# Output_protection.net
KiCad netlist of a schematic drawn in Altium Designer
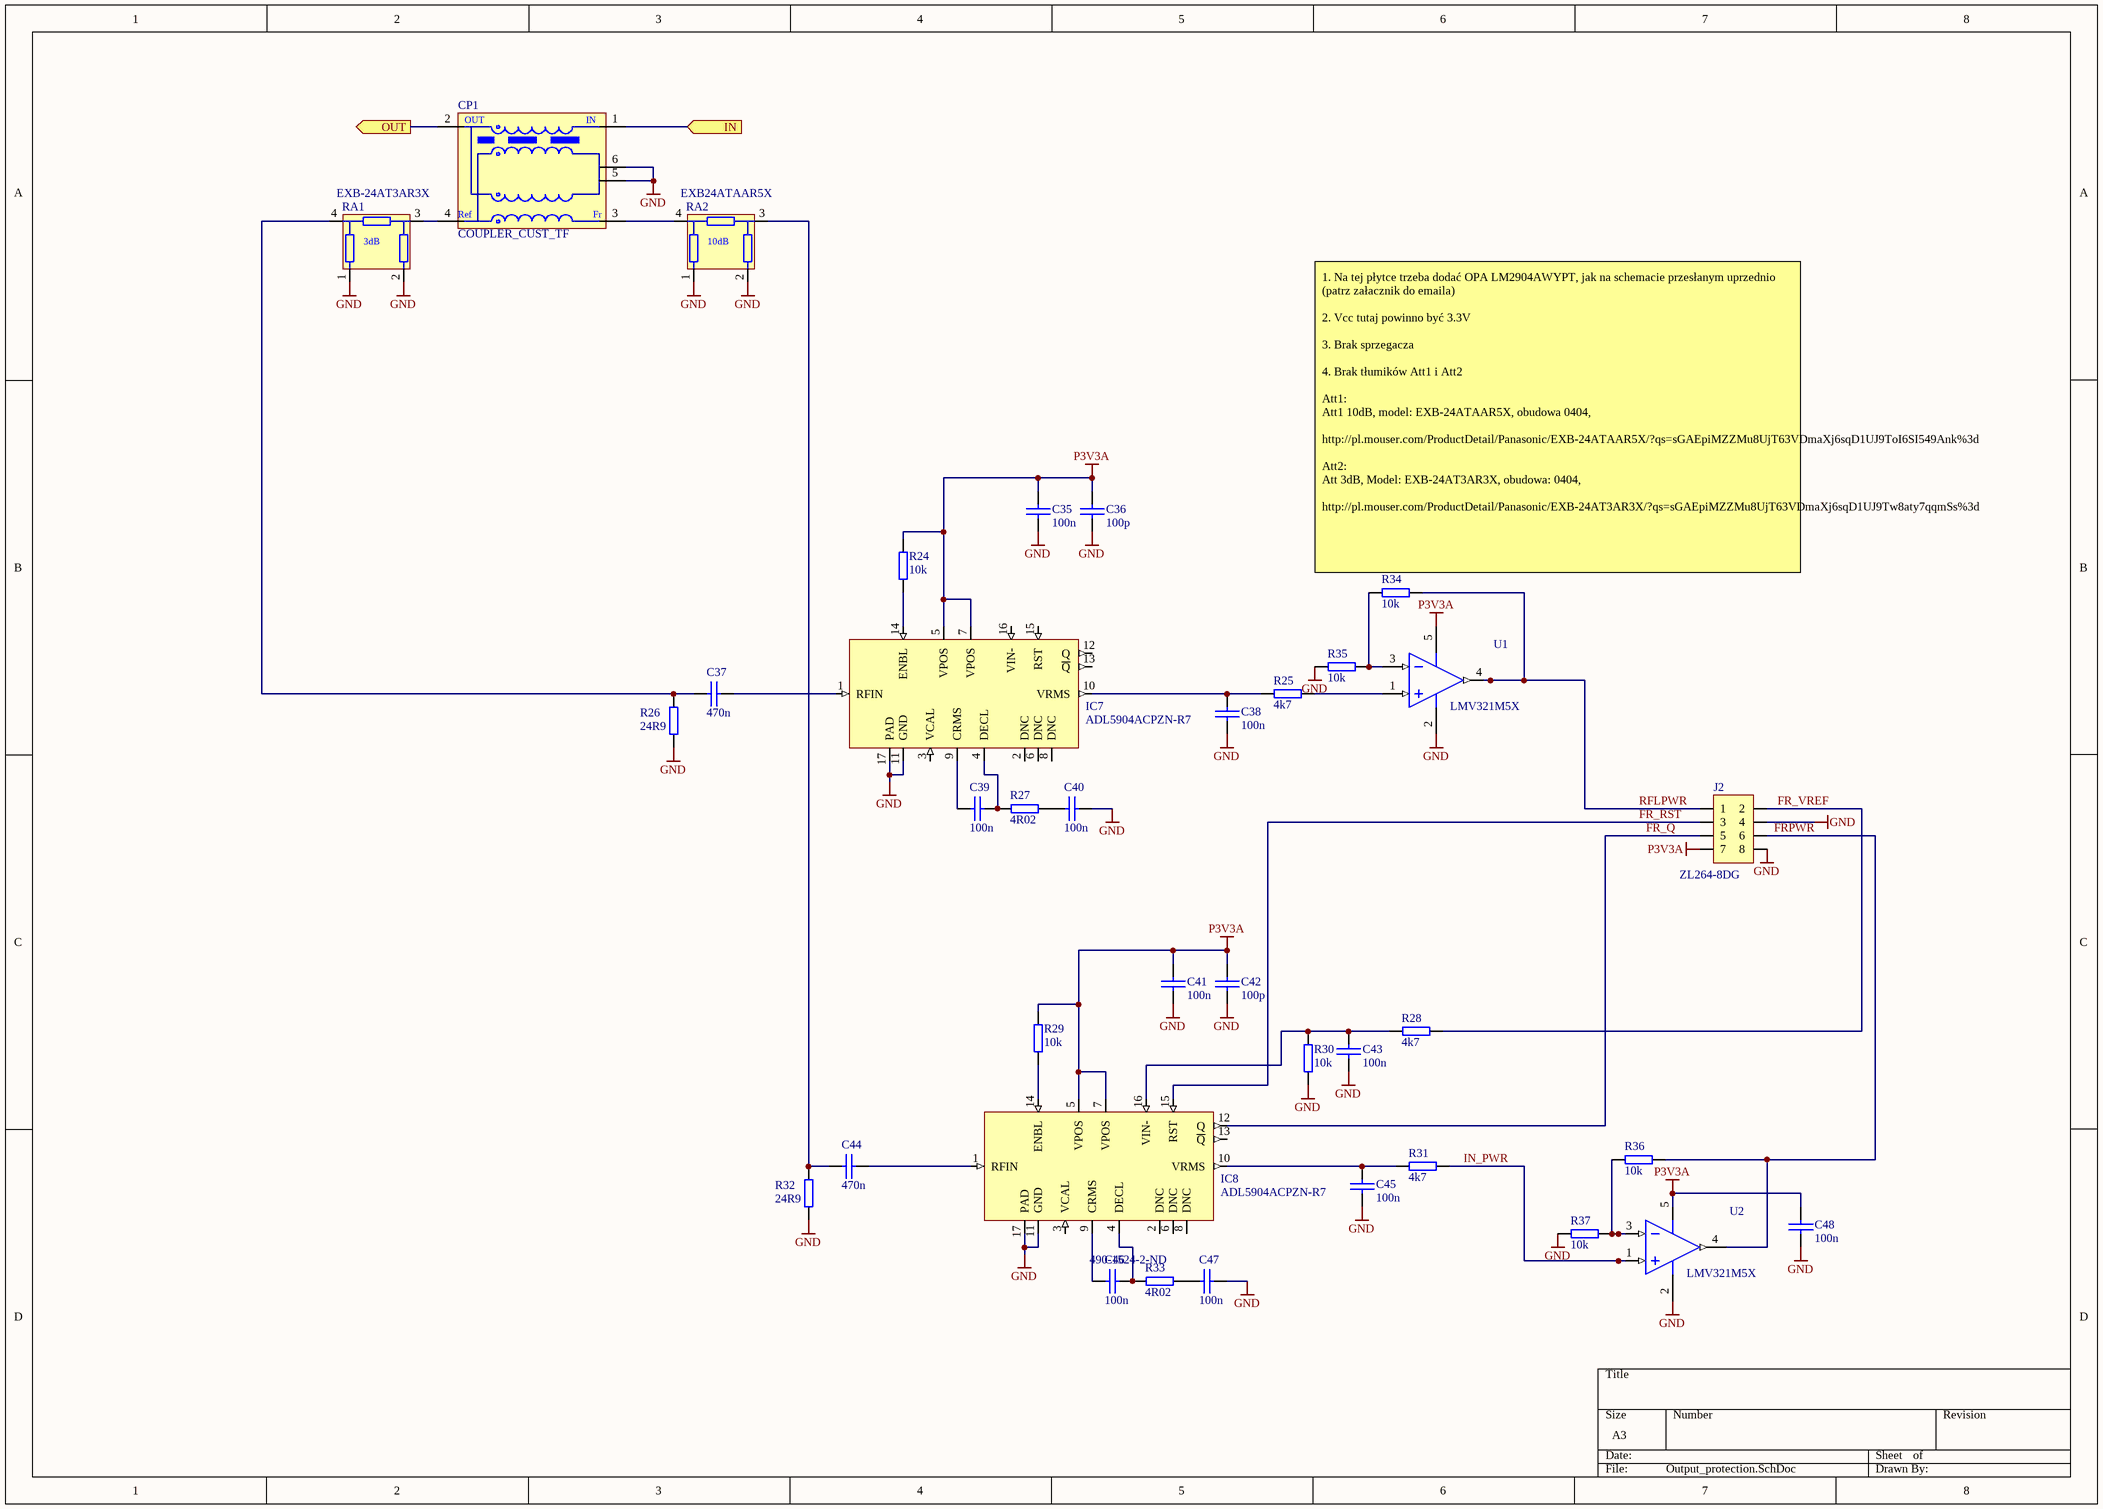
[diagram p0: Output_protection.SchDoc]

(export (version "E")
  (design (tool "Eeschema 10.0.6"))
  (components
    (comp (ref "C35")
      (value "100n")
      (footprint "0603C")
      (description "Capacitor SMD")
      (fields (field (name "PART") "GRM188L81H104KA93D"))
      (libsource (lib "LIBRARY_SCH") (part "CAP_SMD_0603"))
    )
    (comp (ref "C36")
      (value "100p")
      (footprint "0603C")
      (description "Capacitor SMD")
      (fields (field (name "PART") "C1608NP01H101J080AA"))
      (libsource (lib "LIBRARY_SCH") (part "CAP_SMD_0603"))
    )
    (comp (ref "C37")
      (value "470n")
      (footprint "0603C")
      (description "Capacitor SMD")
      (fields (field (name "PART") "GRM188R71A474KA61D"))
      (libsource (lib "LIBRARY_SCH") (part "CAP_SMD_0603"))
    )
    (comp (ref "C38")
      (value "100n")
      (footprint "0603C")
      (description "Capacitor SMD")
      (fields (field (name "PART") "GRM188L81H104KA93D"))
      (libsource (lib "LIBRARY_SCH") (part "CAP_SMD_0603"))
    )
    (comp (ref "C39")
      (value "100n")
      (footprint "0603C")
      (description "Capacitor SMD")
      (fields (field (name "PART") "GRM188L81H104KA93D"))
      (libsource (lib "LIBRARY_SCH") (part "CAP_SMD_0603"))
    )
    (comp (ref "C40")
      (value "100n")
      (footprint "0603C")
      (description "Capacitor SMD")
      (fields (field (name "PART") "GRM188L81H104KA93D"))
      (libsource (lib "LIBRARY_SCH") (part "CAP_SMD_0603"))
    )
    (comp (ref "C41")
      (value "100n")
      (footprint "0603C")
      (description "Capacitor SMD")
      (fields (field (name "PART") "GRM188L81H104KA93D"))
      (libsource (lib "LIBRARY_SCH") (part "CAP_SMD_0603"))
    )
    (comp (ref "C42")
      (value "100p")
      (footprint "0603C")
      (description "Capacitor SMD")
      (fields (field (name "PART") "C1608NP01H101J080AA"))
      (libsource (lib "LIBRARY_SCH") (part "CAP_SMD_0603"))
    )
    (comp (ref "C43")
      (value "100n")
      (footprint "0603C")
      (description "Capacitor SMD")
      (fields (field (name "PART") "GRM188L81H104KA93D"))
      (libsource (lib "LIBRARY_SCH") (part "CAP_SMD_0603"))
    )
    (comp (ref "C44")
      (value "470n")
      (footprint "0603C")
      (description "Capacitor SMD")
      (fields (field (name "PART") "GRM188R71A474KA61D"))
      (libsource (lib "LIBRARY_SCH") (part "CAP_SMD_0603"))
    )
    (comp (ref "C45")
      (value "100n")
      (footprint "0603C")
      (description "Capacitor SMD")
      (fields (field (name "PART") "GRM188L81H104KA93D"))
      (libsource (lib "LIBRARY_SCH") (part "CAP_SMD_0603"))
    )
    (comp (ref "C46")
      (value "100n")
      (footprint "0603C")
      (description "Capacitor SMD")
      (fields
        (field (name "SUPPLIER PART NUMBER 1") "490-1524-2-ND")
        (field (name "PART") "GRM188L81H104KA93D")
      )
      (libsource (lib "LIBRARY_SCH") (part "CAP_SMD_0603"))
    )
    (comp (ref "C47")
      (value "100n")
      (footprint "0603C")
      (description "Capacitor SMD")
      (fields (field (name "PART") "GRM188L81H104KA93D"))
      (libsource (lib "LIBRARY_SCH") (part "CAP_SMD_0603"))
    )
    (comp (ref "C48")
      (value "100n")
      (footprint "0603C")
      (description "Capacitor SMD")
      (fields (field (name "PART") "GRM188L81H104KA93D"))
      (libsource (lib "LIBRARY_SCH") (part "CAP_SMD_0603"))
    )
    (comp (ref "CP1")
      (value "COUPLER_CUST_TF")
      (footprint "COUPLER_CUST_TF")
      (description "custom coupler")
      (libsource (lib "LIBRARY_SCH") (part "IND_COUPLER_TF"))
    )
    (comp (ref "IC7")
      (value "ADL5904ACPZN-R7")
      (footprint "QFN50P300X300X80_HS-17N")
      (description "DC   to 6 GHz  , 45 dB DC  to 6 GHz , 45 dB TruPwr Detector with Envelope Threshold Detection")
      (libsource (lib "LIBRARY_SCH") (part "ADL5904"))
    )
    (comp (ref "IC8")
      (value "ADL5904ACPZN-R7")
      (footprint "QFN50P300X300X80_HS-17N")
      (description "DC   to 6 GHz  , 45 dB DC  to 6 GHz , 45 dB TruPwr Detector with Envelope Threshold Detection")
      (libsource (lib "LIBRARY_SCH") (part "ADL5904"))
    )
    (comp (ref "J2")
      (value "ZL264-8DG")
      (footprint "ZL264-8DG")
      (description "2.54mm pitch connector")
      (libsource (lib "LIBRARY_SCH") (part "CON_2X4 2.54 SMT FEM"))
    )
    (comp (ref "R24")
      (value "10k")
      (footprint "0603R")
      (description "SMD Resistor")
      (fields (field (name "PART") "CRCW060310K0FKEA"))
      (libsource (lib "LIBRARY_SCH") (part "RES_0603"))
    )
    (comp (ref "R25")
      (value "4k7")
      (footprint "0603R")
      (description "SMD Resistor")
      (fields (field (name "PART") "CR0603-FX-4701ELF"))
      (libsource (lib "LIBRARY_SCH") (part "RES_0603"))
    )
    (comp (ref "R26")
      (value "24R9")
      (footprint "0603R")
      (description "SMD Resistor")
      (fields (field (name "PART") "CPF0603F24R9C1"))
      (libsource (lib "LIBRARY_SCH") (part "RES_0603"))
    )
    (comp (ref "R27")
      (value "4R02")
      (footprint "0603R")
      (description "SMD Resistor")
      (fields (field (name "PART") "CRCW06034R02FKEA"))
      (libsource (lib "LIBRARY_SCH") (part "RES_0603"))
    )
    (comp (ref "R28")
      (value "4k7")
      (footprint "0603R")
      (description "SMD Resistor")
      (fields (field (name "PART") "CR0603-FX-4701ELF"))
      (libsource (lib "LIBRARY_SCH") (part "RES_0603"))
    )
    (comp (ref "R29")
      (value "10k")
      (footprint "0603R")
      (description "SMD Resistor")
      (fields (field (name "PART") "CRCW060310K0FKEA"))
      (libsource (lib "LIBRARY_SCH") (part "RES_0603"))
    )
    (comp (ref "R30")
      (value "10k")
      (footprint "0603R")
      (description "SMD Resistor")
      (fields (field (name "PART") "CRCW060310K0FKEA"))
      (libsource (lib "LIBRARY_SCH") (part "RES_0603"))
    )
    (comp (ref "R31")
      (value "4k7")
      (footprint "0603R")
      (description "SMD Resistor")
      (fields (field (name "PART") "CR0603-FX-4701ELF"))
      (libsource (lib "LIBRARY_SCH") (part "RES_0603"))
    )
    (comp (ref "R32")
      (value "24R9")
      (footprint "0603R")
      (description "SMD Resistor")
      (fields (field (name "PART") "CPF0603F24R9C1"))
      (libsource (lib "LIBRARY_SCH") (part "RES_0603"))
    )
    (comp (ref "R33")
      (value "4R02")
      (footprint "0603R")
      (description "SMD Resistor")
      (libsource (lib "LIBRARY_SCH") (part "RES_0603"))
    )
    (comp (ref "R34")
      (value "10k")
      (footprint "0603R")
      (description "SMD Resistor")
      (fields (field (name "PART") "CRCW060310K0FKEA"))
      (libsource (lib "LIBRARY_SCH") (part "RES_0603"))
    )
    (comp (ref "R35")
      (value "10k")
      (footprint "0603R")
      (description "SMD Resistor")
      (fields (field (name "PART") "CRCW060310K0FKEA"))
      (libsource (lib "LIBRARY_SCH") (part "RES_0603"))
    )
    (comp (ref "R36")
      (value "10k")
      (footprint "0603R")
      (description "SMD Resistor")
      (fields (field (name "PART") "CRCW060310K0FKEA"))
      (libsource (lib "LIBRARY_SCH") (part "RES_0603"))
    )
    (comp (ref "R37")
      (value "10k")
      (footprint "0603R")
      (description "SMD Resistor")
      (fields (field (name "PART") "CRCW060310K0FKEA"))
      (libsource (lib "LIBRARY_SCH") (part "RES_0603"))
    )
    (comp (ref "RA1")
      (value "EXB-24AT3AR3X")
      (footprint "CAC-65P100X100-4L")
      (description "3dB Chip Attenuator")
      (libsource (lib "LIBRARY_SCH") (part "RES_ATT_3dB"))
    )
    (comp (ref "RA2")
      (value "EXB24ATAAR5X")
      (footprint "CAC-65P100X100-4L")
      (description "10dB Chip Attenuator")
      (libsource (lib "LIBRARY_SCH") (part "RES_ATT_10dB"))
    )
    (comp (ref "U1")
      (value "LMV321M5X")
      (footprint "DBV0005A_N")
      (description "General Purpose, Low Voltage, Rail-to-Rail Output Operational Amplifiers, 5-pin SOT-23")
      (fields (field (name "MANUFACTURER") "Texas Instruments"))
      (libsource (lib "Altium Content Vault") (part "AMP-OPA-LMV551-5"))
    )
    (comp (ref "U2")
      (value "LMV321M5X")
      (footprint "DBV0005A_N")
      (description "General Purpose, Low Voltage, Rail-to-Rail Output Operational Amplifiers, 5-pin SOT-23")
      (fields (field (name "MANUFACTURER") "Texas Instruments"))
      (libsource (lib "Altium Content Vault") (part "AMP-OPA-LMV551-5"))
    )
  )
  (nets
    (net (code "1") (name "/FRPWR") (class "Default")
      (node (ref "J2") (pin "6") (pinfunction "6_6") (pintype "passive"))
      (node (ref "R36") (pin "1") (pinfunction "1_1") (pintype "passive"))
      (node (ref "U2") (pin "4") (pinfunction "OUT_4") (pintype "output"))
    )
    (net (code "2") (name "/FR_Q") (class "Default")
      (node (ref "IC8") (pin "12") (pinfunction "Q_12") (pintype "output"))
      (node (ref "J2") (pin "5") (pinfunction "5_5") (pintype "passive"))
    )
    (net (code "3") (name "/FR_RST") (class "Default")
      (node (ref "IC8") (pin "15") (pinfunction "RST_15") (pintype "input"))
      (node (ref "J2") (pin "3") (pinfunction "3_3") (pintype "passive"))
    )
    (net (code "4") (name "/FR_VREF") (class "Default")
      (node (ref "J2") (pin "2") (pinfunction "2_2") (pintype "passive"))
      (node (ref "R28") (pin "1") (pinfunction "1_1") (pintype "passive"))
    )
    (net (code "5") (name "/IN") (class "Default") (node (ref "CP1") (pin "1") (pintype "passive")))
    (net (code "6") (name "/IN_PWR") (class "Default")
      (node (ref "R31") (pin "1") (pinfunction "1_1") (pintype "passive"))
      (node (ref "U2") (pin "1") (pinfunction "IN+_1") (pintype "input"))
    )
    (net (code "7") (name "/OUT") (class "Default") (node (ref "CP1") (pin "2") (pintype "passive")))
    (net (code "8") (name "/RFLPWR") (class "Default")
      (node (ref "J2") (pin "1") (pinfunction "1_1") (pintype "passive"))
      (node (ref "R34") (pin "1") (pinfunction "1_1") (pintype "passive"))
      (node (ref "U1") (pin "4") (pinfunction "OUT_4") (pintype "output"))
    )
    (net (code "9") (name "GND") (class "Default")
      (node (ref "C35") (pin "2") (pinfunction "2_2") (pintype "passive"))
      (node (ref "C36") (pin "2") (pinfunction "2_2") (pintype "passive"))
      (node (ref "C38") (pin "1") (pinfunction "1_1") (pintype "passive"))
      (node (ref "C40") (pin "2") (pinfunction "2_2") (pintype "passive"))
      (node (ref "C41") (pin "2") (pinfunction "2_2") (pintype "passive"))
      (node (ref "C42") (pin "2") (pinfunction "2_2") (pintype "passive"))
      (node (ref "C43") (pin "1") (pinfunction "1_1") (pintype "passive"))
      (node (ref "C45") (pin "1") (pinfunction "1_1") (pintype "passive"))
      (node (ref "C47") (pin "2") (pinfunction "2_2") (pintype "passive"))
      (node (ref "C48") (pin "1") (pinfunction "1_1") (pintype "passive"))
      (node (ref "CP1") (pin "5") (pintype "passive"))
      (node (ref "CP1") (pin "6") (pintype "passive"))
      (node (ref "IC7") (pin "11") (pinfunction "GND_11") (pintype "power_in"))
      (node (ref "IC7") (pin "17") (pinfunction "PAD_17") (pintype "power_in"))
      (node (ref "IC8") (pin "11") (pinfunction "GND_11") (pintype "power_in"))
      (node (ref "IC8") (pin "17") (pinfunction "PAD_17") (pintype "power_in"))
      (node (ref "J2") (pin "4") (pinfunction "4_4") (pintype "passive"))
      (node (ref "J2") (pin "8") (pinfunction "8_8") (pintype "passive"))
      (node (ref "R26") (pin "2") (pinfunction "2_2") (pintype "passive"))
      (node (ref "R30") (pin "1") (pinfunction "1_1") (pintype "passive"))
      (node (ref "R32") (pin "2") (pinfunction "2_2") (pintype "passive"))
      (node (ref "R35") (pin "2") (pinfunction "2_2") (pintype "passive"))
      (node (ref "R37") (pin "2") (pinfunction "2_2") (pintype "passive"))
      (node (ref "RA1") (pin "1") (pinfunction "1_1") (pintype "passive"))
      (node (ref "RA1") (pin "2") (pinfunction "2_2") (pintype "passive"))
      (node (ref "RA2") (pin "1") (pinfunction "1_1") (pintype "passive"))
      (node (ref "RA2") (pin "2") (pinfunction "2_2") (pintype "passive"))
      (node (ref "U1") (pin "2") (pinfunction "V-_2") (pintype "power_in"))
      (node (ref "U2") (pin "2") (pinfunction "V-_2") (pintype "power_in"))
    )
    (net (code "10") (name "Net-(C37-Pad1)") (class "Default")
      (node (ref "C37") (pin "1") (pinfunction "1_1") (pintype "passive"))
      (node (ref "R26") (pin "1") (pinfunction "1_1") (pintype "passive"))
      (node (ref "RA1") (pin "4") (pinfunction "4_4") (pintype "passive"))
    )
    (net (code "11") (name "Net-(C40-Pad1)") (class "Default")
      (node (ref "C40") (pin "1") (pinfunction "1_1") (pintype "passive"))
      (node (ref "R27") (pin "2") (pinfunction "2_2") (pintype "passive"))
    )
    (net (code "12") (name "Net-(C44-Pad1)") (class "Default")
      (node (ref "C44") (pin "1") (pinfunction "1_1") (pintype "passive"))
      (node (ref "R32") (pin "1") (pinfunction "1_1") (pintype "passive"))
      (node (ref "RA2") (pin "3") (pinfunction "3_3") (pintype "passive"))
    )
    (net (code "13") (name "Net-(C47-Pad1)") (class "Default")
      (node (ref "C47") (pin "1") (pinfunction "1_1") (pintype "passive"))
      (node (ref "R33") (pin "2") (pinfunction "2_2") (pintype "passive"))
    )
    (net (code "14") (name "Net-(CP1-Pad3)") (class "Default")
      (node (ref "CP1") (pin "3") (pintype "passive"))
      (node (ref "RA2") (pin "4") (pinfunction "4_4") (pintype "passive"))
    )
    (net (code "15") (name "Net-(CP1-Pad4)") (class "Default")
      (node (ref "CP1") (pin "4") (pintype "passive"))
      (node (ref "RA1") (pin "3") (pinfunction "3_3") (pintype "passive"))
    )
    (net (code "16") (name "Net-(IC7-CRMS)") (class "Default")
      (node (ref "C39") (pin "1") (pinfunction "1_1") (pintype "passive"))
      (node (ref "IC7") (pin "9") (pinfunction "CRMS_9") (pintype "passive"))
    )
    (net (code "17") (name "Net-(IC7-DECL)") (class "Default")
      (node (ref "C39") (pin "2") (pinfunction "2_2") (pintype "passive"))
      (node (ref "IC7") (pin "4") (pinfunction "DECL_4") (pintype "passive"))
      (node (ref "R27") (pin "1") (pinfunction "1_1") (pintype "passive"))
    )
    (net (code "18") (name "Net-(IC7-ENBL)") (class "Default")
      (node (ref "IC7") (pin "14") (pinfunction "ENBL_14") (pintype "input"))
      (node (ref "R24") (pin "2") (pinfunction "2_2") (pintype "passive"))
    )
    (net (code "19") (name "Net-(IC7-RFIN)") (class "Default")
      (node (ref "C37") (pin "2") (pinfunction "2_2") (pintype "passive"))
      (node (ref "IC7") (pin "1") (pinfunction "RFIN_1") (pintype "input"))
    )
    (net (code "20") (name "Net-(IC7-VRMS)") (class "Default")
      (node (ref "C38") (pin "2") (pinfunction "2_2") (pintype "passive"))
      (node (ref "IC7") (pin "10") (pinfunction "VRMS_10") (pintype "output"))
      (node (ref "R25") (pin "2") (pinfunction "2_2") (pintype "passive"))
    )
    (net (code "21") (name "Net-(IC8-CRMS)") (class "Default")
      (node (ref "C46") (pin "1") (pinfunction "1_1") (pintype "passive"))
      (node (ref "IC8") (pin "9") (pinfunction "CRMS_9") (pintype "passive"))
    )
    (net (code "22") (name "Net-(IC8-DECL)") (class "Default")
      (node (ref "C46") (pin "2") (pinfunction "2_2") (pintype "passive"))
      (node (ref "IC8") (pin "4") (pinfunction "DECL_4") (pintype "passive"))
      (node (ref "R33") (pin "1") (pinfunction "1_1") (pintype "passive"))
    )
    (net (code "23") (name "Net-(IC8-ENBL)") (class "Default")
      (node (ref "IC8") (pin "14") (pinfunction "ENBL_14") (pintype "input"))
      (node (ref "R29") (pin "2") (pinfunction "2_2") (pintype "passive"))
    )
    (net (code "24") (name "Net-(IC8-RFIN)") (class "Default")
      (node (ref "C44") (pin "2") (pinfunction "2_2") (pintype "passive"))
      (node (ref "IC8") (pin "1") (pinfunction "RFIN_1") (pintype "input"))
    )
    (net (code "25") (name "Net-(IC8-VIN-)") (class "Default")
      (node (ref "C43") (pin "2") (pinfunction "2_2") (pintype "passive"))
      (node (ref "IC8") (pin "16") (pinfunction "VIN-_16") (pintype "input"))
      (node (ref "R28") (pin "2") (pinfunction "2_2") (pintype "passive"))
      (node (ref "R30") (pin "2") (pinfunction "2_2") (pintype "passive"))
    )
    (net (code "26") (name "Net-(IC8-VRMS)") (class "Default")
      (node (ref "C45") (pin "2") (pinfunction "2_2") (pintype "passive"))
      (node (ref "IC8") (pin "10") (pinfunction "VRMS_10") (pintype "output"))
      (node (ref "R31") (pin "2") (pinfunction "2_2") (pintype "passive"))
    )
    (net (code "27") (name "Net-(U1-IN+)") (class "Default")
      (node (ref "R25") (pin "1") (pinfunction "1_1") (pintype "passive"))
      (node (ref "U1") (pin "1") (pinfunction "IN+_1") (pintype "input"))
    )
    (net (code "28") (name "Net-(U1-IN-)") (class "Default")
      (node (ref "R34") (pin "2") (pinfunction "2_2") (pintype "passive"))
      (node (ref "R35") (pin "1") (pinfunction "1_1") (pintype "passive"))
      (node (ref "U1") (pin "3") (pinfunction "IN-_3") (pintype "input"))
    )
    (net (code "29") (name "Net-(U2-IN-)") (class "Default")
      (node (ref "R36") (pin "2") (pinfunction "2_2") (pintype "passive"))
      (node (ref "R37") (pin "1") (pinfunction "1_1") (pintype "passive"))
      (node (ref "U2") (pin "3") (pinfunction "IN-_3") (pintype "input"))
    )
    (net (code "30") (name "P3V3A") (class "Default")
      (node (ref "C35") (pin "1") (pinfunction "1_1") (pintype "passive"))
      (node (ref "C36") (pin "1") (pinfunction "1_1") (pintype "passive"))
      (node (ref "C41") (pin "1") (pinfunction "1_1") (pintype "passive"))
      (node (ref "C42") (pin "1") (pinfunction "1_1") (pintype "passive"))
      (node (ref "C48") (pin "2") (pinfunction "2_2") (pintype "passive"))
      (node (ref "IC7") (pin "5") (pinfunction "VPOS_5") (pintype "power_in"))
      (node (ref "IC7") (pin "7") (pinfunction "VPOS_7") (pintype "power_in"))
      (node (ref "IC8") (pin "5") (pinfunction "VPOS_5") (pintype "power_in"))
      (node (ref "IC8") (pin "7") (pinfunction "VPOS_7") (pintype "power_in"))
      (node (ref "J2") (pin "7") (pinfunction "7_7") (pintype "passive"))
      (node (ref "R24") (pin "1") (pinfunction "1_1") (pintype "passive"))
      (node (ref "R29") (pin "1") (pinfunction "1_1") (pintype "passive"))
      (node (ref "U1") (pin "5") (pinfunction "V+_5") (pintype "power_in"))
      (node (ref "U2") (pin "5") (pinfunction "V+_5") (pintype "power_in"))
    )
    (net (code "31") (name "unconnected-(IC7-DNC-Pad2)") (class "Default")
      (node (ref "IC7") (pin "2") (pinfunction "DNC_2") (pintype "passive"))
    )
    (net (code "32") (name "unconnected-(IC7-DNC-Pad6)") (class "Default")
      (node (ref "IC7") (pin "6") (pinfunction "DNC_6") (pintype "passive"))
    )
    (net (code "33") (name "unconnected-(IC7-DNC-Pad8)") (class "Default")
      (node (ref "IC7") (pin "8") (pinfunction "DNC_8") (pintype "passive"))
    )
    (net (code "34") (name "unconnected-(IC7-Q-Pad12)") (class "Default")
      (node (ref "IC7") (pin "12") (pinfunction "Q_12") (pintype "output"))
    )
    (net (code "35") (name "unconnected-(IC7-RST-Pad15)") (class "Default")
      (node (ref "IC7") (pin "15") (pinfunction "RST_15") (pintype "input"))
    )
    (net (code "36") (name "unconnected-(IC7-VCAL-Pad3)") (class "Default")
      (node (ref "IC7") (pin "3") (pinfunction "VCAL_3") (pintype "input"))
    )
    (net (code "37") (name "unconnected-(IC7-VIN--Pad16)") (class "Default")
      (node (ref "IC7") (pin "16") (pinfunction "VIN-_16") (pintype "input"))
    )
    (net (code "38") (name "unconnected-(IC7-~{Q}-Pad13)") (class "Default")
      (node (ref "IC7") (pin "13") (pinfunction "~{Q}_13") (pintype "output"))
    )
    (net (code "39") (name "unconnected-(IC8-DNC-Pad2)") (class "Default")
      (node (ref "IC8") (pin "2") (pinfunction "DNC_2") (pintype "passive"))
    )
    (net (code "40") (name "unconnected-(IC8-DNC-Pad6)") (class "Default")
      (node (ref "IC8") (pin "6") (pinfunction "DNC_6") (pintype "passive"))
    )
    (net (code "41") (name "unconnected-(IC8-DNC-Pad8)") (class "Default")
      (node (ref "IC8") (pin "8") (pinfunction "DNC_8") (pintype "passive"))
    )
    (net (code "42") (name "unconnected-(IC8-VCAL-Pad3)") (class "Default")
      (node (ref "IC8") (pin "3") (pinfunction "VCAL_3") (pintype "input"))
    )
    (net (code "43") (name "unconnected-(IC8-~{Q}-Pad13)") (class "Default")
      (node (ref "IC8") (pin "13") (pinfunction "~{Q}_13") (pintype "output"))
    )
  )
)
